# Outputs.net
KiCad netlist of a schematic drawn in Altium Designer
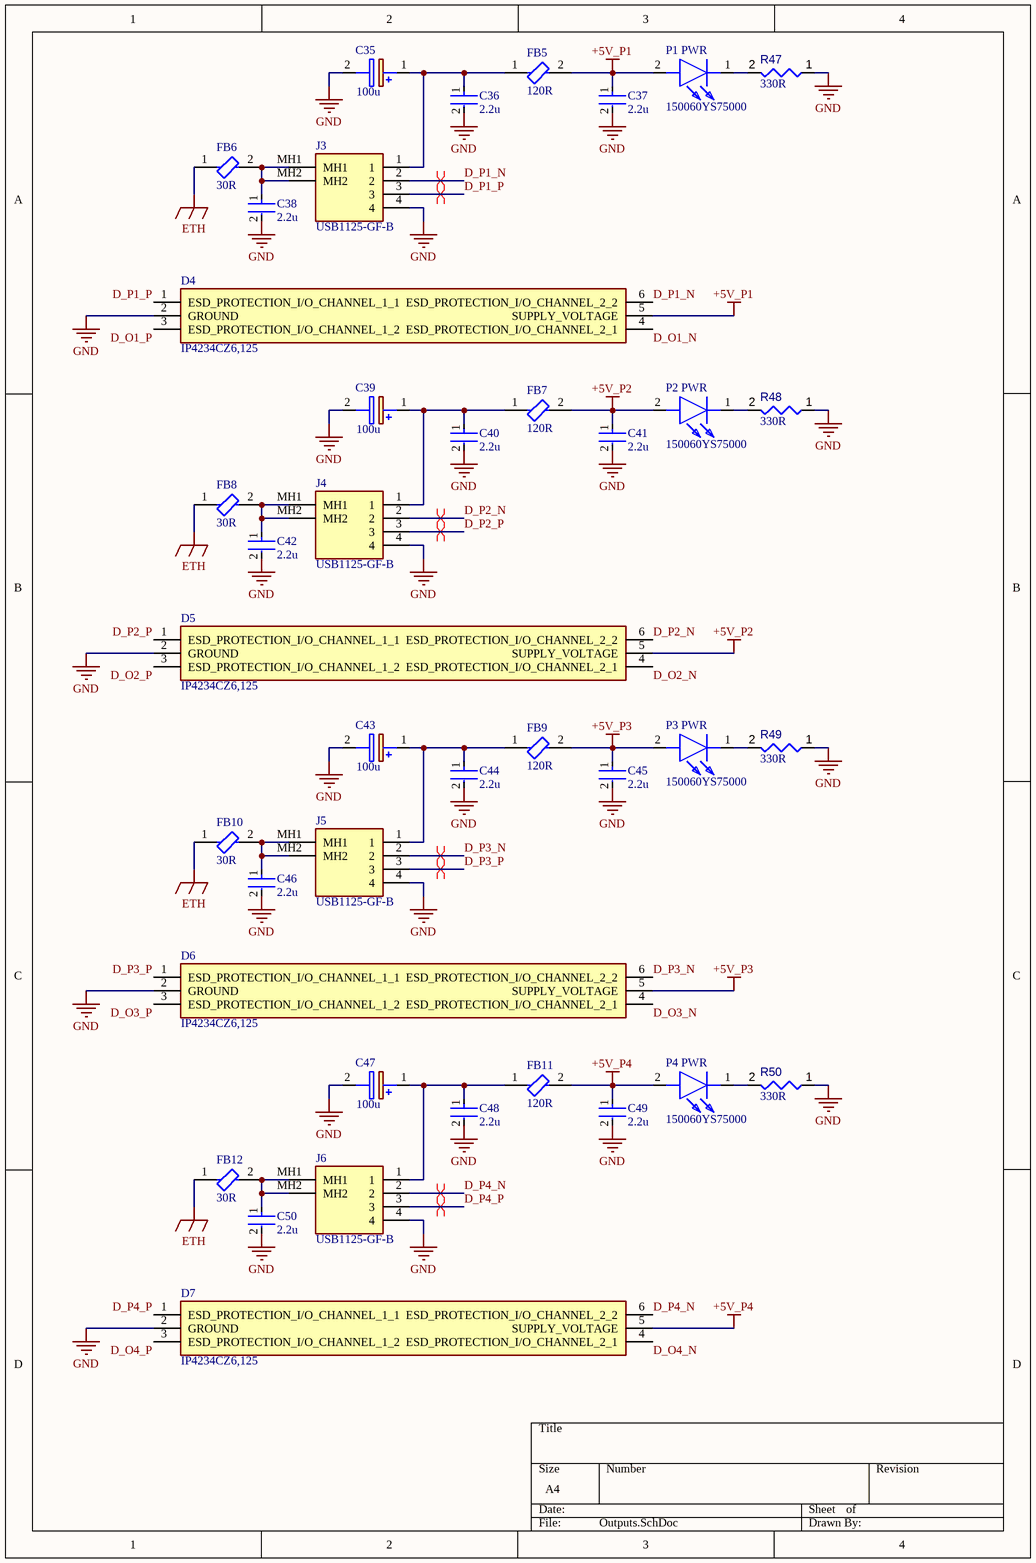
[diagram p0: Outputs.SchDoc]

(export (version "E")
  (design (tool "Eeschema 10.0.6"))
  (components
    (comp (ref "C35")
      (value "100u")
      (footprint "SamacSys:CAPPM7343X310N")
      (description "Capacitor Polarised")
      (fields
        (field (name "MANUFACTURER_PART_NUMBER") "293D107X0016D2TE3")
        (field (name "MOUSER PART NUMBER") "74-293D107X0016D2TE3")
      )
      (libsource (lib "*") (part "293D107X0016D2TE3"))
    )
    (comp (ref "C36")
      (value "0603 CAP")
      (footprint "PCB1:0603-C")
      (fields
        (field (name "VOLTAGE") "6.3V")
        (field (name "TOLERANCE") "20%")
        (field (name "MANUFACTURER") "Murata")
        (field (name "CAPACITANCE") "2.2u")
      )
      (libsource (lib "Personal Library") (part "CMP-2006-02792-2"))
    )
    (comp (ref "C37")
      (value "0603 CAP")
      (footprint "PCB1:0603-C")
      (fields
        (field (name "VOLTAGE") "6.3V")
        (field (name "TOLERANCE") "20%")
        (field (name "MANUFACTURER") "Murata")
        (field (name "CAPACITANCE") "2.2u")
      )
      (libsource (lib "Personal Library") (part "CMP-2006-02792-2"))
    )
    (comp (ref "C38")
      (value "0603 CAP")
      (footprint "PCB1:0603-C")
      (fields
        (field (name "VOLTAGE") "6.3V")
        (field (name "TOLERANCE") "20%")
        (field (name "MANUFACTURER") "Murata")
        (field (name "CAPACITANCE") "2.2u")
      )
      (libsource (lib "Personal Library") (part "CMP-2006-02792-2"))
    )
    (comp (ref "C39")
      (value "100u")
      (footprint "CAPPM7343X310N")
      (description "Capacitor Polarised")
      (fields
        (field (name "MANUFACTURER_PART_NUMBER") "293D107X0016D2TE3")
        (field (name "MOUSER PART NUMBER") "74-293D107X0016D2TE3")
      )
      (libsource (lib "*") (part "293D107X0016D2TE3"))
    )
    (comp (ref "C40")
      (value "0603 CAP")
      (footprint "PCB1:0603-C")
      (fields
        (field (name "VOLTAGE") "6.3V")
        (field (name "TOLERANCE") "20%")
        (field (name "MANUFACTURER") "Murata")
        (field (name "CAPACITANCE") "2.2u")
      )
      (libsource (lib "Personal Library") (part "CMP-2006-02792-2"))
    )
    (comp (ref "C41")
      (value "0603 CAP")
      (footprint "PCB1:0603-C")
      (fields
        (field (name "VOLTAGE") "6.3V")
        (field (name "TOLERANCE") "20%")
        (field (name "MANUFACTURER") "Murata")
        (field (name "CAPACITANCE") "2.2u")
      )
      (libsource (lib "Personal Library") (part "CMP-2006-02792-2"))
    )
    (comp (ref "C42")
      (value "0603 CAP")
      (footprint "PCB1:0603-C")
      (fields
        (field (name "VOLTAGE") "6.3V")
        (field (name "TOLERANCE") "20%")
        (field (name "MANUFACTURER") "Murata")
        (field (name "CAPACITANCE") "2.2u")
      )
      (libsource (lib "Personal Library") (part "CMP-2006-02792-2"))
    )
    (comp (ref "C43")
      (value "100u")
      (footprint "SamacSys:CAPPM7343X310N")
      (description "Capacitor Polarised")
      (fields
        (field (name "MANUFACTURER_PART_NUMBER") "293D107X0016D2TE3")
        (field (name "MOUSER PART NUMBER") "74-293D107X0016D2TE3")
      )
      (libsource (lib "*") (part "293D107X0016D2TE3"))
    )
    (comp (ref "C44")
      (value "0603 CAP")
      (footprint "PCB1:0603-C")
      (fields
        (field (name "VOLTAGE") "6.3V")
        (field (name "TOLERANCE") "20%")
        (field (name "MANUFACTURER") "Murata")
        (field (name "CAPACITANCE") "2.2u")
      )
      (libsource (lib "Personal Library") (part "CMP-2006-02792-2"))
    )
    (comp (ref "C45")
      (value "0603 CAP")
      (footprint "PCB1:0603-C")
      (fields
        (field (name "VOLTAGE") "6.3V")
        (field (name "TOLERANCE") "20%")
        (field (name "MANUFACTURER") "Murata")
        (field (name "CAPACITANCE") "2.2u")
      )
      (libsource (lib "Personal Library") (part "CMP-2006-02792-2"))
    )
    (comp (ref "C46")
      (value "0603 CAP")
      (footprint "PCB1:0603-C")
      (fields
        (field (name "VOLTAGE") "6.3V")
        (field (name "TOLERANCE") "20%")
        (field (name "MANUFACTURER") "Murata")
        (field (name "CAPACITANCE") "2.2u")
      )
      (libsource (lib "Personal Library") (part "CMP-2006-02792-2"))
    )
    (comp (ref "C47")
      (value "100u")
      (footprint "SamacSys:CAPPM7343X310N")
      (description "Capacitor Polarised")
      (fields
        (field (name "MANUFACTURER_PART_NUMBER") "293D107X0016D2TE3")
        (field (name "MOUSER PART NUMBER") "74-293D107X0016D2TE3")
      )
      (libsource (lib "*") (part "293D107X0016D2TE3"))
    )
    (comp (ref "C48")
      (value "0603 CAP")
      (footprint "PCB1:0603-C")
      (fields
        (field (name "VOLTAGE") "6.3V")
        (field (name "TOLERANCE") "20%")
        (field (name "MANUFACTURER") "Murata")
        (field (name "CAPACITANCE") "2.2u")
      )
      (libsource (lib "Personal Library") (part "CMP-2006-02792-2"))
    )
    (comp (ref "C49")
      (value "0603 CAP")
      (footprint "PCB1:0603-C")
      (fields
        (field (name "VOLTAGE") "6.3V")
        (field (name "TOLERANCE") "20%")
        (field (name "MANUFACTURER") "Murata")
        (field (name "CAPACITANCE") "2.2u")
      )
      (libsource (lib "Personal Library") (part "CMP-2006-02792-2"))
    )
    (comp (ref "C50")
      (value "0603 CAP")
      (footprint "PCB1:0603-C")
      (fields
        (field (name "VOLTAGE") "6.3V")
        (field (name "TOLERANCE") "20%")
        (field (name "MANUFACTURER") "Murata")
        (field (name "CAPACITANCE") "2.2u")
      )
      (libsource (lib "Personal Library") (part "CMP-2006-02792-2"))
    )
    (comp (ref "D4")
      (value "IP4234CZ6,125")
      (footprint "SamacSys:SOP95P275X110-6N")
      (description "Diode")
      (fields (field (name "MOUSER PART NUMBER") "771-IP4234CZ6125"))
      (libsource (lib "*") (part "IP4234CZ6,125"))
    )
    (comp (ref "D5")
      (value "IP4234CZ6,125")
      (footprint "SamacSys:SOP95P275X110-6N")
      (description "Diode")
      (fields (field (name "MOUSER PART NUMBER") "771-IP4234CZ6125"))
      (libsource (lib "*") (part "IP4234CZ6,125"))
    )
    (comp (ref "D6")
      (value "IP4234CZ6,125")
      (footprint "SamacSys:SOP95P275X110-6N")
      (description "Diode")
      (fields (field (name "MOUSER PART NUMBER") "771-IP4234CZ6125"))
      (libsource (lib "*") (part "IP4234CZ6,125"))
    )
    (comp (ref "D7")
      (value "IP4234CZ6,125")
      (footprint "SamacSys:SOP95P275X110-6N")
      (description "Diode")
      (fields (field (name "MOUSER PART NUMBER") "771-IP4234CZ6125"))
      (libsource (lib "*") (part "IP4234CZ6,125"))
    )
    (comp (ref "FB5")
      (value "120R")
      (footprint "FP-ILHB-0805-IPC_C")
      (description "FERRITE BEAD 600 OHM 0805 1LN")
      (fields
        (field (name "TOLERANCE") "25%")
        (field (name "OCTOPART") "https://octopart.com/ilhb0805er601v-vishay-39650184")
      )
      (libsource (lib "Altium Content Vault") (part "5f30dd21d616792df468990f7003faa"))
    )
    (comp (ref "FB6")
      (value "30R")
      (footprint "FP-BLM18-0_15-t0_6-d1_2-MFG")
      (description "Chip Ferrite Bead Array, 0603, 30Ω @ 100MHz, 25%, 0.01Ω, 5A")
      (fields (field (name "TOLERANCE") "25%"))
      (libsource (lib "Altium Content Vault") (part "5f30dd21d616792df468990f7003faa"))
    )
    (comp (ref "FB7")
      (value "120R")
      (footprint "FP-ILHB-0805-IPC_C")
      (description "FERRITE BEAD 600 OHM 0805 1LN")
      (fields
        (field (name "TOLERANCE") "25%")
        (field (name "OCTOPART") "https://octopart.com/ilhb0805er601v-vishay-39650184")
      )
      (libsource (lib "Altium Content Vault") (part "5f30dd21d616792df468990f7003faa"))
    )
    (comp (ref "FB8")
      (value "30R")
      (footprint "FP-BLM18-0_15-t0_6-d1_2-MFG")
      (description "Chip Ferrite Bead Array, 0603, 30Ω @ 100MHz, 25%, 0.01Ω, 5A")
      (fields (field (name "TOLERANCE") "25%"))
      (libsource (lib "Altium Content Vault") (part "5f30dd21d616792df468990f7003faa"))
    )
    (comp (ref "FB9")
      (value "120R")
      (footprint "FP-ILHB-0805-IPC_C")
      (description "FERRITE BEAD 600 OHM 0805 1LN")
      (fields
        (field (name "TOLERANCE") "25%")
        (field (name "OCTOPART") "https://octopart.com/ilhb0805er601v-vishay-39650184")
      )
      (libsource (lib "Altium Content Vault") (part "5f30dd21d616792df468990f7003faa"))
    )
    (comp (ref "FB10")
      (value "30R")
      (footprint "FP-BLM18-0_15-t0_6-d1_2-MFG")
      (description "Chip Ferrite Bead Array, 0603, 30Ω @ 100MHz, 25%, 0.01Ω, 5A")
      (fields (field (name "TOLERANCE") "25%"))
      (libsource (lib "Altium Content Vault") (part "5f30dd21d616792df468990f7003faa"))
    )
    (comp (ref "FB11")
      (value "120R")
      (footprint "FP-ILHB-0805-IPC_C")
      (description "FERRITE BEAD 600 OHM 0805 1LN")
      (fields
        (field (name "TOLERANCE") "25%")
        (field (name "OCTOPART") "https://octopart.com/ilhb0805er601v-vishay-39650184")
      )
      (libsource (lib "Altium Content Vault") (part "5f30dd21d616792df468990f7003faa"))
    )
    (comp (ref "FB12")
      (value "30R")
      (footprint "FP-BLM18-0_15-t0_6-d1_2-MFG")
      (description "Chip Ferrite Bead Array, 0603, 30Ω @ 100MHz, 25%, 0.01Ω, 5A")
      (fields (field (name "TOLERANCE") "25%"))
      (libsource (lib "Altium Content Vault") (part "5f30dd21d616792df468990f7003faa"))
    )
    (comp (ref "J3")
      (value "USB1125-GF-B")
      (footprint "SamacSys:USB1125GFB")
      (description "Connector")
      (fields (field (name "MOUSER PART NUMBER") "640-USB1125-GF-B"))
      (libsource (lib "*") (part "USB1125-GF-B"))
    )
    (comp (ref "J4")
      (value "USB1125-GF-B")
      (footprint "SamacSys:USB1125GFB")
      (description "Connector")
      (fields (field (name "MOUSER PART NUMBER") "640-USB1125-GF-B"))
      (libsource (lib "*") (part "USB1125-GF-B"))
    )
    (comp (ref "J5")
      (value "USB1125-GF-B")
      (footprint "SamacSys:USB1125GFB")
      (description "Connector")
      (fields (field (name "MOUSER PART NUMBER") "640-USB1125-GF-B"))
      (libsource (lib "*") (part "USB1125-GF-B"))
    )
    (comp (ref "J6")
      (value "USB1125-GF-B")
      (footprint "SamacSys:USB1125GFB")
      (description "Connector")
      (fields (field (name "MOUSER PART NUMBER") "640-USB1125-GF-B"))
      (libsource (lib "*") (part "USB1125-GF-B"))
    )
    (comp (ref "P1 PWR")
      (value "150060YS75000")
      (footprint "SamacSys:LEDC1608X80N")
      (description "LED")
      (fields (field (name "MOUSER PART NUMBER") "710-150060YS75000"))
      (libsource (lib "*") (part "150060YS75000"))
    )
    (comp (ref "P2 PWR")
      (value "150060YS75000")
      (footprint "SamacSys:LEDC1608X80N")
      (description "LED")
      (fields (field (name "MOUSER PART NUMBER") "710-150060YS75000"))
      (libsource (lib "*") (part "150060YS75000"))
    )
    (comp (ref "P3 PWR")
      (value "150060YS75000")
      (footprint "SamacSys:LEDC1608X80N")
      (description "LED")
      (fields (field (name "MOUSER PART NUMBER") "710-150060YS75000"))
      (libsource (lib "*") (part "150060YS75000"))
    )
    (comp (ref "P4 PWR")
      (value "150060YS75000")
      (footprint "SamacSys:LEDC1608X80N")
      (description "LED")
      (fields (field (name "MOUSER PART NUMBER") "710-150060YS75000"))
      (libsource (lib "*") (part "150060YS75000"))
    )
    (comp (ref "R47")
      (value "330R")
      (footprint "PCB1:0603-R")
      (description "0603 Resistor")
      (fields (field (name "POWER") "100mW") (field (name "TOLERANCE") "1%"))
      (libsource (lib "Personal Library") (part "CMP-009-00014-5"))
    )
    (comp (ref "R48")
      (value "330R")
      (footprint "PCB1:0603-R")
      (description "0603 Resistor")
      (fields (field (name "POWER") "100mW") (field (name "TOLERANCE") "1%"))
      (libsource (lib "Personal Library") (part "CMP-009-00014-5"))
    )
    (comp (ref "R49")
      (value "330R")
      (footprint "PCB1:0603-R")
      (description "0603 Resistor")
      (fields (field (name "POWER") "100mW") (field (name "TOLERANCE") "1%"))
      (libsource (lib "Personal Library") (part "CMP-009-00014-5"))
    )
    (comp (ref "R50")
      (value "330R")
      (footprint "PCB1:0603-R")
      (description "0603 Resistor")
      (fields (field (name "POWER") "100mW") (field (name "TOLERANCE") "1%"))
      (libsource (lib "Personal Library") (part "CMP-009-00014-5"))
    )
  )
  (nets
    (net (code "1") (name "+5V_P1") (class "Default")
      (node (ref "C37") (pin "1") (pinfunction "1_1") (pintype "passive"))
      (node (ref "D4") (pin "5") (pinfunction "SUPPLY_VOLTAGE_5") (pintype "passive"))
      (node (ref "FB5") (pin "2") (pinfunction "2_2") (pintype "passive"))
      (node (ref "P1 PWR") (pin "2") (pinfunction "A_2") (pintype "passive"))
    )
    (net (code "2") (name "+5V_P2") (class "Default")
      (node (ref "C41") (pin "1") (pinfunction "1_1") (pintype "passive"))
      (node (ref "D5") (pin "5") (pinfunction "SUPPLY_VOLTAGE_5") (pintype "passive"))
      (node (ref "FB7") (pin "2") (pinfunction "2_2") (pintype "passive"))
      (node (ref "P2 PWR") (pin "2") (pinfunction "A_2") (pintype "passive"))
    )
    (net (code "3") (name "+5V_P3") (class "Default")
      (node (ref "C45") (pin "1") (pinfunction "1_1") (pintype "passive"))
      (node (ref "D6") (pin "5") (pinfunction "SUPPLY_VOLTAGE_5") (pintype "passive"))
      (node (ref "FB9") (pin "2") (pinfunction "2_2") (pintype "passive"))
      (node (ref "P3 PWR") (pin "2") (pinfunction "A_2") (pintype "passive"))
    )
    (net (code "4") (name "+5V_P4") (class "Default")
      (node (ref "C49") (pin "1") (pinfunction "1_1") (pintype "passive"))
      (node (ref "D7") (pin "5") (pinfunction "SUPPLY_VOLTAGE_5") (pintype "passive"))
      (node (ref "FB11") (pin "2") (pinfunction "2_2") (pintype "passive"))
      (node (ref "P4 PWR") (pin "2") (pinfunction "A_2") (pintype "passive"))
    )
    (net (code "5") (name "/D_O1_N") (class "Default")
      (node (ref "D4") (pin "4") (pinfunction "ESD_PROTECTION_I/O_CHANNEL_2_1_4") (pintype "passive"))
    )
    (net (code "6") (name "/D_O1_P") (class "Default")
      (node (ref "D4") (pin "3") (pinfunction "ESD_PROTECTION_I/O_CHANNEL_1_2_3") (pintype "passive"))
    )
    (net (code "7") (name "/D_O2_N") (class "Default")
      (node (ref "D5") (pin "4") (pinfunction "ESD_PROTECTION_I/O_CHANNEL_2_1_4") (pintype "passive"))
    )
    (net (code "8") (name "/D_O2_P") (class "Default")
      (node (ref "D5") (pin "3") (pinfunction "ESD_PROTECTION_I/O_CHANNEL_1_2_3") (pintype "passive"))
    )
    (net (code "9") (name "/D_O3_N") (class "Default")
      (node (ref "D6") (pin "4") (pinfunction "ESD_PROTECTION_I/O_CHANNEL_2_1_4") (pintype "passive"))
    )
    (net (code "10") (name "/D_O3_P") (class "Default")
      (node (ref "D6") (pin "3") (pinfunction "ESD_PROTECTION_I/O_CHANNEL_1_2_3") (pintype "passive"))
    )
    (net (code "11") (name "/D_O4_N") (class "Default")
      (node (ref "D7") (pin "4") (pinfunction "ESD_PROTECTION_I/O_CHANNEL_2_1_4") (pintype "passive"))
    )
    (net (code "12") (name "/D_O4_P") (class "Default")
      (node (ref "D7") (pin "3") (pinfunction "ESD_PROTECTION_I/O_CHANNEL_1_2_3") (pintype "passive"))
    )
    (net (code "13") (name "/D_P1_N") (class "Default")
      (node (ref "D4") (pin "6") (pinfunction "ESD_PROTECTION_I/O_CHANNEL_2_2_6") (pintype "passive"))
      (node (ref "J3") (pin "2") (pinfunction "2_2") (pintype "passive"))
    )
    (net (code "14") (name "/D_P1_P") (class "Default")
      (node (ref "D4") (pin "1") (pinfunction "ESD_PROTECTION_I/O_CHANNEL_1_1_1") (pintype "passive"))
      (node (ref "J3") (pin "3") (pinfunction "3_3") (pintype "passive"))
    )
    (net (code "15") (name "/D_P2_N") (class "Default")
      (node (ref "D5") (pin "6") (pinfunction "ESD_PROTECTION_I/O_CHANNEL_2_2_6") (pintype "passive"))
      (node (ref "J4") (pin "2") (pinfunction "2_2") (pintype "passive"))
    )
    (net (code "16") (name "/D_P2_P") (class "Default")
      (node (ref "D5") (pin "1") (pinfunction "ESD_PROTECTION_I/O_CHANNEL_1_1_1") (pintype "passive"))
      (node (ref "J4") (pin "3") (pinfunction "3_3") (pintype "passive"))
    )
    (net (code "17") (name "/D_P3_N") (class "Default")
      (node (ref "D6") (pin "6") (pinfunction "ESD_PROTECTION_I/O_CHANNEL_2_2_6") (pintype "passive"))
      (node (ref "J5") (pin "2") (pinfunction "2_2") (pintype "passive"))
    )
    (net (code "18") (name "/D_P3_P") (class "Default")
      (node (ref "D6") (pin "1") (pinfunction "ESD_PROTECTION_I/O_CHANNEL_1_1_1") (pintype "passive"))
      (node (ref "J5") (pin "3") (pinfunction "3_3") (pintype "passive"))
    )
    (net (code "19") (name "/D_P4_N") (class "Default")
      (node (ref "D7") (pin "6") (pinfunction "ESD_PROTECTION_I/O_CHANNEL_2_2_6") (pintype "passive"))
      (node (ref "J6") (pin "2") (pinfunction "2_2") (pintype "passive"))
    )
    (net (code "20") (name "/D_P4_P") (class "Default")
      (node (ref "D7") (pin "1") (pinfunction "ESD_PROTECTION_I/O_CHANNEL_1_1_1") (pintype "passive"))
      (node (ref "J6") (pin "3") (pinfunction "3_3") (pintype "passive"))
    )
    (net (code "21") (name "ETH") (class "Default")
      (node (ref "FB10") (pin "1") (pinfunction "1_1") (pintype "passive"))
      (node (ref "FB12") (pin "1") (pinfunction "1_1") (pintype "passive"))
      (node (ref "FB6") (pin "1") (pinfunction "1_1") (pintype "passive"))
      (node (ref "FB8") (pin "1") (pinfunction "1_1") (pintype "passive"))
    )
    (net (code "22") (name "GND") (class "Default")
      (node (ref "C35") (pin "2") (pinfunction "-_2") (pintype "passive"))
      (node (ref "C36") (pin "2") (pinfunction "2_2") (pintype "passive"))
      (node (ref "C37") (pin "2") (pinfunction "2_2") (pintype "passive"))
      (node (ref "C38") (pin "2") (pinfunction "2_2") (pintype "passive"))
      (node (ref "C39") (pin "2") (pinfunction "-_2") (pintype "passive"))
      (node (ref "C40") (pin "2") (pinfunction "2_2") (pintype "passive"))
      (node (ref "C41") (pin "2") (pinfunction "2_2") (pintype "passive"))
      (node (ref "C42") (pin "2") (pinfunction "2_2") (pintype "passive"))
      (node (ref "C43") (pin "2") (pinfunction "-_2") (pintype "passive"))
      (node (ref "C44") (pin "2") (pinfunction "2_2") (pintype "passive"))
      (node (ref "C45") (pin "2") (pinfunction "2_2") (pintype "passive"))
      (node (ref "C46") (pin "2") (pinfunction "2_2") (pintype "passive"))
      (node (ref "C47") (pin "2") (pinfunction "-_2") (pintype "passive"))
      (node (ref "C48") (pin "2") (pinfunction "2_2") (pintype "passive"))
      (node (ref "C49") (pin "2") (pinfunction "2_2") (pintype "passive"))
      (node (ref "C50") (pin "2") (pinfunction "2_2") (pintype "passive"))
      (node (ref "D4") (pin "2") (pinfunction "GROUND_2") (pintype "passive"))
      (node (ref "D5") (pin "2") (pinfunction "GROUND_2") (pintype "passive"))
      (node (ref "D6") (pin "2") (pinfunction "GROUND_2") (pintype "passive"))
      (node (ref "D7") (pin "2") (pinfunction "GROUND_2") (pintype "passive"))
      (node (ref "J3") (pin "4") (pinfunction "4_4") (pintype "passive"))
      (node (ref "J4") (pin "4") (pinfunction "4_4") (pintype "passive"))
      (node (ref "J5") (pin "4") (pinfunction "4_4") (pintype "passive"))
      (node (ref "J6") (pin "4") (pinfunction "4_4") (pintype "passive"))
      (node (ref "R47") (pin "1") (pinfunction "1_1") (pintype "passive"))
      (node (ref "R48") (pin "1") (pinfunction "1_1") (pintype "passive"))
      (node (ref "R49") (pin "1") (pinfunction "1_1") (pintype "passive"))
      (node (ref "R50") (pin "1") (pinfunction "1_1") (pintype "passive"))
    )
    (net (code "23") (name "Net-(C35-+)") (class "Default")
      (node (ref "C35") (pin "1") (pinfunction "+_1") (pintype "passive"))
      (node (ref "C36") (pin "1") (pinfunction "1_1") (pintype "passive"))
      (node (ref "FB5") (pin "1") (pinfunction "1_1") (pintype "passive"))
      (node (ref "J3") (pin "1") (pinfunction "1_1") (pintype "passive"))
    )
    (net (code "24") (name "Net-(C38-Pad1)") (class "Default")
      (node (ref "C38") (pin "1") (pinfunction "1_1") (pintype "passive"))
      (node (ref "FB6") (pin "2") (pinfunction "2_2") (pintype "passive"))
      (node (ref "J3") (pin "MH1") (pinfunction "MH1_MH1") (pintype "passive"))
      (node (ref "J3") (pin "MH2") (pinfunction "MH2_MH2") (pintype "passive"))
    )
    (net (code "25") (name "Net-(C39-+)") (class "Default")
      (node (ref "C39") (pin "1") (pinfunction "+_1") (pintype "passive"))
      (node (ref "C40") (pin "1") (pinfunction "1_1") (pintype "passive"))
      (node (ref "FB7") (pin "1") (pinfunction "1_1") (pintype "passive"))
      (node (ref "J4") (pin "1") (pinfunction "1_1") (pintype "passive"))
    )
    (net (code "26") (name "Net-(C42-Pad1)") (class "Default")
      (node (ref "C42") (pin "1") (pinfunction "1_1") (pintype "passive"))
      (node (ref "FB8") (pin "2") (pinfunction "2_2") (pintype "passive"))
      (node (ref "J4") (pin "MH1") (pinfunction "MH1_MH1") (pintype "passive"))
      (node (ref "J4") (pin "MH2") (pinfunction "MH2_MH2") (pintype "passive"))
    )
    (net (code "27") (name "Net-(C43-+)") (class "Default")
      (node (ref "C43") (pin "1") (pinfunction "+_1") (pintype "passive"))
      (node (ref "C44") (pin "1") (pinfunction "1_1") (pintype "passive"))
      (node (ref "FB9") (pin "1") (pinfunction "1_1") (pintype "passive"))
      (node (ref "J5") (pin "1") (pinfunction "1_1") (pintype "passive"))
    )
    (net (code "28") (name "Net-(C46-Pad1)") (class "Default")
      (node (ref "C46") (pin "1") (pinfunction "1_1") (pintype "passive"))
      (node (ref "FB10") (pin "2") (pinfunction "2_2") (pintype "passive"))
      (node (ref "J5") (pin "MH1") (pinfunction "MH1_MH1") (pintype "passive"))
      (node (ref "J5") (pin "MH2") (pinfunction "MH2_MH2") (pintype "passive"))
    )
    (net (code "29") (name "Net-(C47-+)") (class "Default")
      (node (ref "C47") (pin "1") (pinfunction "+_1") (pintype "passive"))
      (node (ref "C48") (pin "1") (pinfunction "1_1") (pintype "passive"))
      (node (ref "FB11") (pin "1") (pinfunction "1_1") (pintype "passive"))
      (node (ref "J6") (pin "1") (pinfunction "1_1") (pintype "passive"))
    )
    (net (code "30") (name "Net-(C50-Pad1)") (class "Default")
      (node (ref "C50") (pin "1") (pinfunction "1_1") (pintype "passive"))
      (node (ref "FB12") (pin "2") (pinfunction "2_2") (pintype "passive"))
      (node (ref "J6") (pin "MH1") (pinfunction "MH1_MH1") (pintype "passive"))
      (node (ref "J6") (pin "MH2") (pinfunction "MH2_MH2") (pintype "passive"))
    )
    (net (code "31") (name "Net-(P1 PWR-K)") (class "Default")
      (node (ref "P1 PWR") (pin "1") (pinfunction "K_1") (pintype "passive"))
      (node (ref "R47") (pin "2") (pinfunction "2_2") (pintype "passive"))
    )
    (net (code "32") (name "Net-(P2 PWR-K)") (class "Default")
      (node (ref "P2 PWR") (pin "1") (pinfunction "K_1") (pintype "passive"))
      (node (ref "R48") (pin "2") (pinfunction "2_2") (pintype "passive"))
    )
    (net (code "33") (name "Net-(P3 PWR-K)") (class "Default")
      (node (ref "P3 PWR") (pin "1") (pinfunction "K_1") (pintype "passive"))
      (node (ref "R49") (pin "2") (pinfunction "2_2") (pintype "passive"))
    )
    (net (code "34") (name "Net-(P4 PWR-K)") (class "Default")
      (node (ref "P4 PWR") (pin "1") (pinfunction "K_1") (pintype "passive"))
      (node (ref "R50") (pin "2") (pinfunction "2_2") (pintype "passive"))
    )
  )
)
